# SPIDER.net
KiCad netlist of a schematic drawn in EAGLE
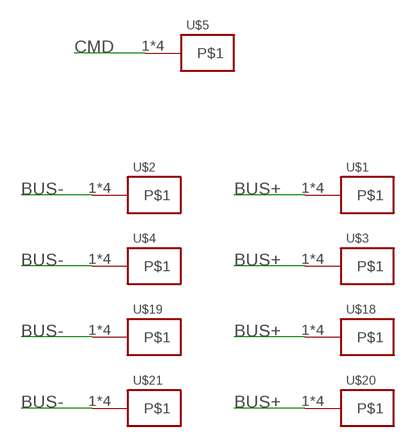
[diagram p0: schematic, sheet 1]

(export (version "E")
  (design (tool "Eeschema 10.0.6"))
  (components
    (comp (ref "U$1")
      (value "KCONNECT-")
      (footprint "eagle-import:KCONNECT-")
      (libsource (lib "eagle-import") (part "KCONNECT-"))
    )
    (comp (ref "U$2")
      (value "KCONNECT-")
      (footprint "eagle-import:KCONNECT-")
      (libsource (lib "eagle-import") (part "KCONNECT-"))
    )
    (comp (ref "U$3")
      (value "KCONNECT-")
      (footprint "eagle-import:KCONNECT-")
      (libsource (lib "eagle-import") (part "KCONNECT-"))
    )
    (comp (ref "U$4")
      (value "KCONNECT-")
      (footprint "eagle-import:KCONNECT-")
      (libsource (lib "eagle-import") (part "KCONNECT-"))
    )
    (comp (ref "U$5")
      (value "KCONNECTQUAD-")
      (footprint "eagle-import:KCONNECT-_QUAD")
      (libsource (lib "eagle-import") (part "KCONNECTQUAD-"))
    )
    (comp (ref "U$18")
      (value "KCONNECT-")
      (footprint "eagle-import:KCONNECT-")
      (libsource (lib "eagle-import") (part "KCONNECT-"))
    )
    (comp (ref "U$19")
      (value "KCONNECT-")
      (footprint "eagle-import:KCONNECT-")
      (libsource (lib "eagle-import") (part "KCONNECT-"))
    )
    (comp (ref "U$20")
      (value "KCONNECT-")
      (footprint "eagle-import:KCONNECT-")
      (libsource (lib "eagle-import") (part "KCONNECT-"))
    )
    (comp (ref "U$21")
      (value "KCONNECT-")
      (footprint "eagle-import:KCONNECT-")
      (libsource (lib "eagle-import") (part "KCONNECT-"))
    )
  )
  (nets
    (net (code "1") (name "/BUS+") (class "Default")
      (node (ref "U$1") (pin "1") (pinfunction "P$1_1") (pintype "bidirectional"))
      (node (ref "U$1") (pin "2") (pinfunction "P$1_2") (pintype "bidirectional"))
      (node (ref "U$1") (pin "3") (pinfunction "P$1_3") (pintype "bidirectional"))
      (node (ref "U$1") (pin "4") (pinfunction "P$1_4") (pintype "bidirectional"))
      (node (ref "U$18") (pin "1") (pinfunction "P$1_1") (pintype "bidirectional"))
      (node (ref "U$18") (pin "2") (pinfunction "P$1_2") (pintype "bidirectional"))
      (node (ref "U$18") (pin "3") (pinfunction "P$1_3") (pintype "bidirectional"))
      (node (ref "U$18") (pin "4") (pinfunction "P$1_4") (pintype "bidirectional"))
      (node (ref "U$20") (pin "1") (pinfunction "P$1_1") (pintype "bidirectional"))
      (node (ref "U$20") (pin "2") (pinfunction "P$1_2") (pintype "bidirectional"))
      (node (ref "U$20") (pin "3") (pinfunction "P$1_3") (pintype "bidirectional"))
      (node (ref "U$20") (pin "4") (pinfunction "P$1_4") (pintype "bidirectional"))
      (node (ref "U$3") (pin "1") (pinfunction "P$1_1") (pintype "bidirectional"))
      (node (ref "U$3") (pin "2") (pinfunction "P$1_2") (pintype "bidirectional"))
      (node (ref "U$3") (pin "3") (pinfunction "P$1_3") (pintype "bidirectional"))
      (node (ref "U$3") (pin "4") (pinfunction "P$1_4") (pintype "bidirectional"))
    )
    (net (code "2") (name "/BUS-") (class "Default")
      (node (ref "U$19") (pin "1") (pinfunction "P$1_1") (pintype "bidirectional"))
      (node (ref "U$19") (pin "2") (pinfunction "P$1_2") (pintype "bidirectional"))
      (node (ref "U$19") (pin "3") (pinfunction "P$1_3") (pintype "bidirectional"))
      (node (ref "U$19") (pin "4") (pinfunction "P$1_4") (pintype "bidirectional"))
      (node (ref "U$2") (pin "1") (pinfunction "P$1_1") (pintype "bidirectional"))
      (node (ref "U$2") (pin "2") (pinfunction "P$1_2") (pintype "bidirectional"))
      (node (ref "U$2") (pin "3") (pinfunction "P$1_3") (pintype "bidirectional"))
      (node (ref "U$2") (pin "4") (pinfunction "P$1_4") (pintype "bidirectional"))
      (node (ref "U$21") (pin "1") (pinfunction "P$1_1") (pintype "bidirectional"))
      (node (ref "U$21") (pin "2") (pinfunction "P$1_2") (pintype "bidirectional"))
      (node (ref "U$21") (pin "3") (pinfunction "P$1_3") (pintype "bidirectional"))
      (node (ref "U$21") (pin "4") (pinfunction "P$1_4") (pintype "bidirectional"))
      (node (ref "U$4") (pin "1") (pinfunction "P$1_1") (pintype "bidirectional"))
      (node (ref "U$4") (pin "2") (pinfunction "P$1_2") (pintype "bidirectional"))
      (node (ref "U$4") (pin "3") (pinfunction "P$1_3") (pintype "bidirectional"))
      (node (ref "U$4") (pin "4") (pinfunction "P$1_4") (pintype "bidirectional"))
    )
    (net (code "3") (name "/CMD") (class "Default")
      (node (ref "U$5") (pin "1") (pinfunction "P$1_1") (pintype "bidirectional"))
      (node (ref "U$5") (pin "2") (pinfunction "P$1_2") (pintype "bidirectional"))
      (node (ref "U$5") (pin "3") (pinfunction "P$1_3") (pintype "bidirectional"))
      (node (ref "U$5") (pin "4") (pinfunction "P$1_4") (pintype "bidirectional"))
    )
  )
)
